# LB_BIT_o9_BARGRAPH-v02_rev1.net
KiCad netlist of a schematic drawn in EAGLE
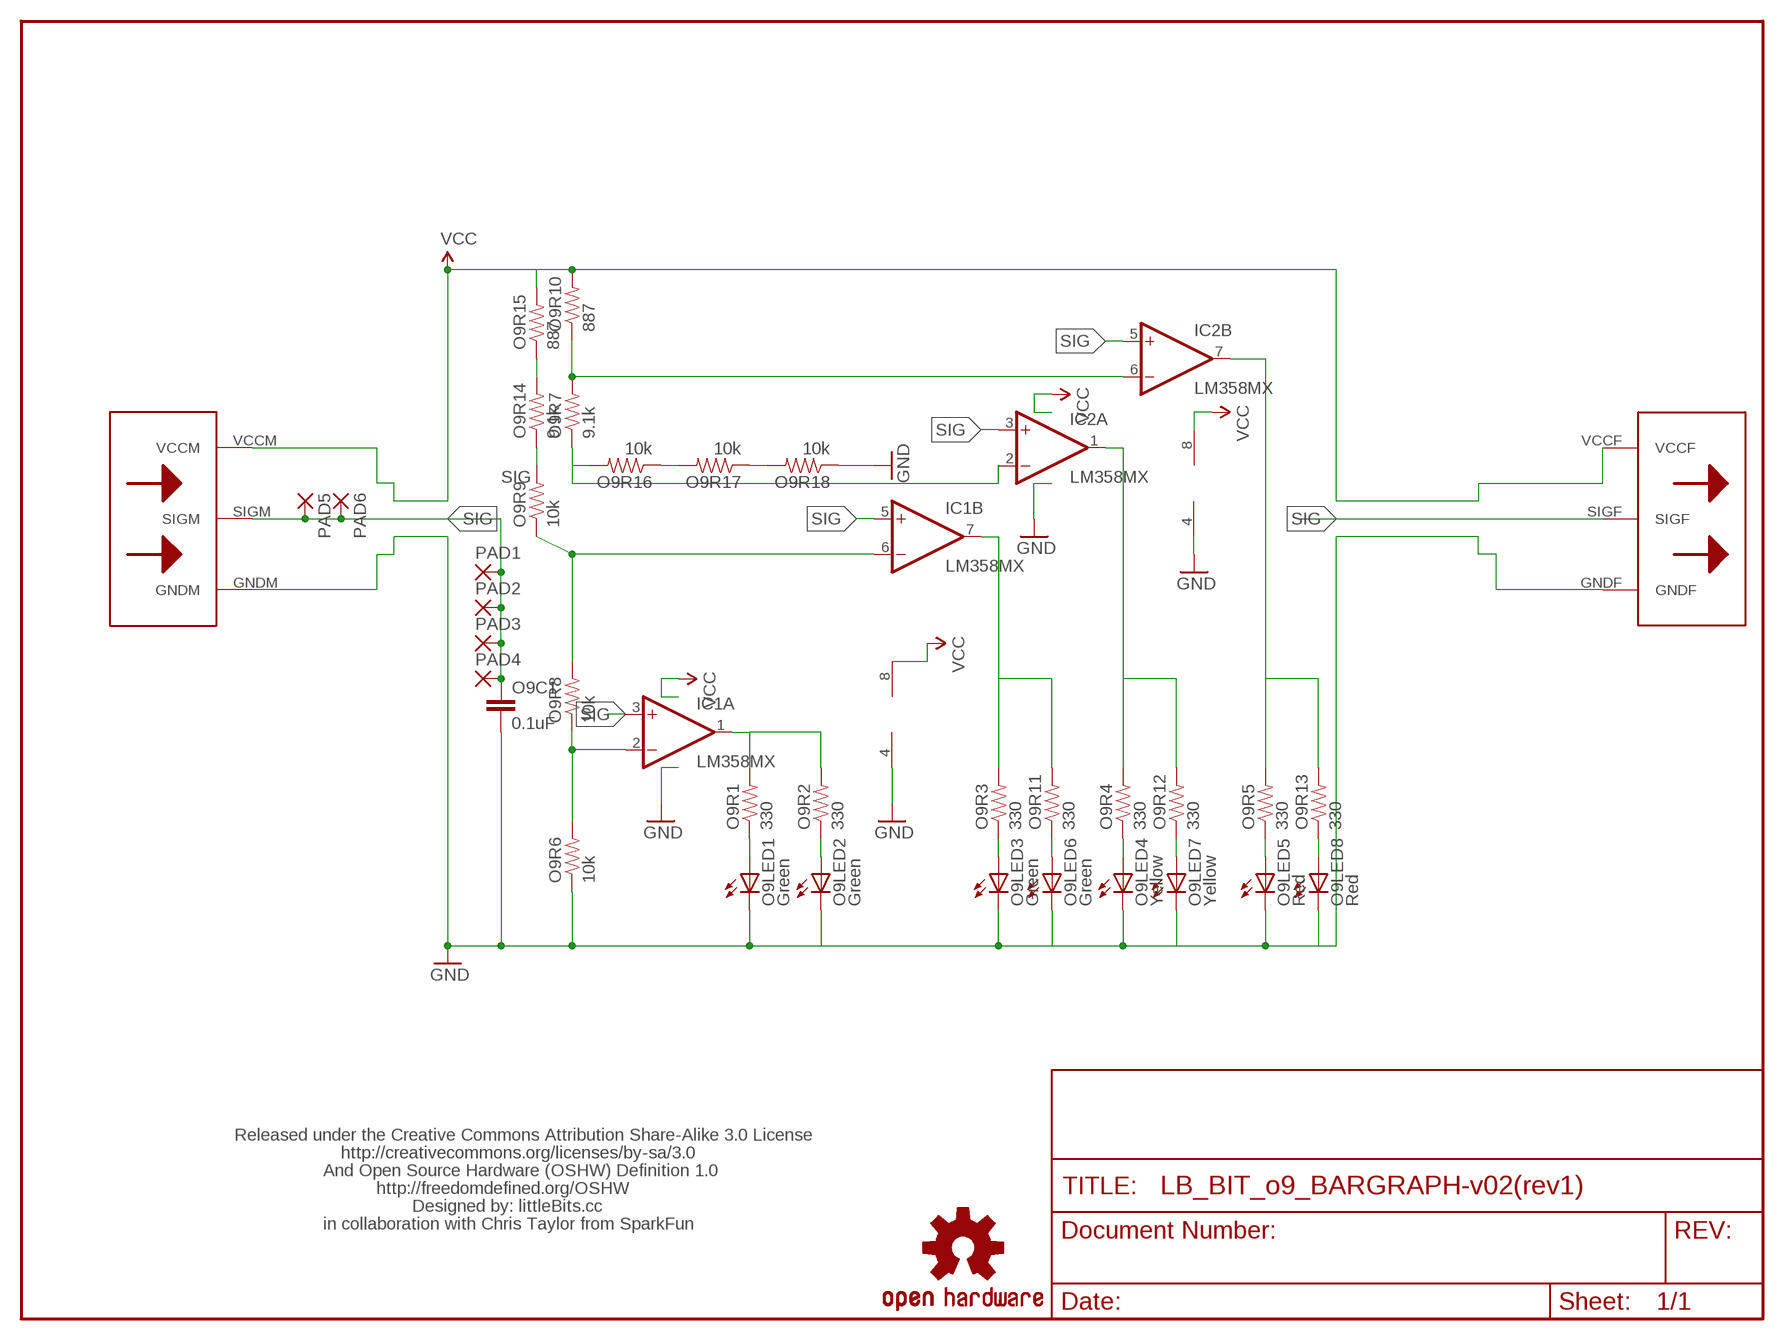
[diagram p0: schematic, sheet 1]

(export (version "E")
  (design (tool "Eeschema 10.0.6"))
  (components
    (comp (ref "IC1")
      (value "LM358MX")
      (footprint "eagle-import:SO08")
      (libsource (lib "eagle-import") (part "LM358MX"))
    )
    (comp (ref "IC2")
      (value "LM358MX")
      (footprint "eagle-import:SO08")
      (libsource (lib "eagle-import") (part "LM358MX"))
    )
    (comp (ref "O9C1")
      (value "0.1uF")
      (footprint "eagle-import:0603-CAP")
      (libsource (lib "eagle-import") (part "CAP0603-CAP"))
    )
    (comp (ref "O9LED1")
      (value "Green")
      (footprint "eagle-import:LED-1206")
      (libsource (lib "eagle-import") (part "LED1206"))
    )
    (comp (ref "O9LED2")
      (value "Green")
      (footprint "eagle-import:LED-1206")
      (libsource (lib "eagle-import") (part "LED1206"))
    )
    (comp (ref "O9LED3")
      (value "Green")
      (footprint "eagle-import:LED-1206")
      (libsource (lib "eagle-import") (part "LED1206"))
    )
    (comp (ref "O9LED4")
      (value "Yellow")
      (footprint "eagle-import:LED-1206")
      (libsource (lib "eagle-import") (part "LED1206"))
    )
    (comp (ref "O9LED5")
      (value "Red")
      (footprint "eagle-import:LED-1206")
      (libsource (lib "eagle-import") (part "LED1206"))
    )
    (comp (ref "O9LED6")
      (value "Green")
      (footprint "eagle-import:LED-1206")
      (libsource (lib "eagle-import") (part "LED1206"))
    )
    (comp (ref "O9LED7")
      (value "Yellow")
      (footprint "eagle-import:LED-1206")
      (libsource (lib "eagle-import") (part "LED1206"))
    )
    (comp (ref "O9LED8")
      (value "Red")
      (footprint "eagle-import:LED-1206")
      (libsource (lib "eagle-import") (part "LED1206"))
    )
    (comp (ref "O9R1")
      (value "330")
      (footprint "eagle-import:0805")
      (libsource (lib "eagle-import") (part "RESISTOR"))
    )
    (comp (ref "O9R2")
      (value "330")
      (footprint "eagle-import:0805")
      (libsource (lib "eagle-import") (part "RESISTOR"))
    )
    (comp (ref "O9R3")
      (value "330")
      (footprint "eagle-import:0805")
      (libsource (lib "eagle-import") (part "RESISTOR"))
    )
    (comp (ref "O9R4")
      (value "330")
      (footprint "eagle-import:0805")
      (libsource (lib "eagle-import") (part "RESISTOR"))
    )
    (comp (ref "O9R5")
      (value "330")
      (footprint "eagle-import:0805")
      (libsource (lib "eagle-import") (part "RESISTOR"))
    )
    (comp (ref "O9R6")
      (value "10k")
      (footprint "eagle-import:0805")
      (libsource (lib "eagle-import") (part "RESISTOR"))
    )
    (comp (ref "O9R7")
      (value "9.1k")
      (footprint "eagle-import:0805")
      (libsource (lib "eagle-import") (part "RESISTOR"))
    )
    (comp (ref "O9R8")
      (value "10k")
      (footprint "eagle-import:0805")
      (libsource (lib "eagle-import") (part "RESISTOR"))
    )
    (comp (ref "O9R9")
      (value "10k")
      (footprint "eagle-import:0805")
      (libsource (lib "eagle-import") (part "RESISTOR"))
    )
    (comp (ref "O9R10")
      (value "887")
      (footprint "eagle-import:0805")
      (libsource (lib "eagle-import") (part "RESISTOR"))
    )
    (comp (ref "O9R11")
      (value "330")
      (footprint "eagle-import:0805")
      (libsource (lib "eagle-import") (part "RESISTOR"))
    )
    (comp (ref "O9R12")
      (value "330")
      (footprint "eagle-import:0805")
      (libsource (lib "eagle-import") (part "RESISTOR"))
    )
    (comp (ref "O9R13")
      (value "330")
      (footprint "eagle-import:0805")
      (libsource (lib "eagle-import") (part "RESISTOR"))
    )
    (comp (ref "O9R14")
      (value "9.1k")
      (footprint "eagle-import:0805")
      (libsource (lib "eagle-import") (part "RESISTOR"))
    )
    (comp (ref "O9R15")
      (value "887")
      (footprint "eagle-import:0805")
      (libsource (lib "eagle-import") (part "RESISTOR"))
    )
    (comp (ref "O9R16")
      (value "10k")
      (footprint "eagle-import:0805")
      (libsource (lib "eagle-import") (part "RESISTOR"))
    )
    (comp (ref "O9R17")
      (value "10k")
      (footprint "eagle-import:0805")
      (libsource (lib "eagle-import") (part "RESISTOR"))
    )
    (comp (ref "O9R18")
      (value "10k")
      (footprint "eagle-import:0805")
      (libsource (lib "eagle-import") (part "RESISTOR"))
    )
    (comp (ref "PAD1")
      (value "SMD2")
      (footprint "eagle-import:SMD1,27-2,54")
      (libsource (lib "eagle-import") (part "SMD2"))
    )
    (comp (ref "PAD2")
      (value "SMD2")
      (footprint "eagle-import:SMD1,27-2,54")
      (libsource (lib "eagle-import") (part "SMD2"))
    )
    (comp (ref "PAD3")
      (value "SMD2")
      (footprint "eagle-import:SMD1,27-2,54")
      (libsource (lib "eagle-import") (part "SMD2"))
    )
    (comp (ref "PAD4")
      (value "SMD2")
      (footprint "eagle-import:SMD1,27-2,54")
      (libsource (lib "eagle-import") (part "SMD2"))
    )
    (comp (ref "PAD5")
      (value "SMD2")
      (footprint "eagle-import:SMD1,27-2,54")
      (libsource (lib "eagle-import") (part "SMD2"))
    )
    (comp (ref "PAD6")
      (value "SMD2")
      (footprint "eagle-import:SMD1,27-2,54")
      (libsource (lib "eagle-import") (part "SMD2"))
    )
    (comp (ref "U$1")
      (value "LB_CREDITS")
      (footprint "eagle-import:OSHWCREDIT")
      (libsource (lib "eagle-import") (part "LB_CREDITS"))
    )
    (comp (ref "U$3")
      (value "OSHW-LOGOL")
      (footprint "eagle-import:OSHW-LOGO-L")
      (libsource (lib "eagle-import") (part "OSHW-LOGOL"))
    )
    (comp (ref "U$7")
      (value "BIGBIT")
      (footprint "eagle-import:BIGBIT")
      (libsource (lib "eagle-import") (part "BIGBIT"))
    )
  )
  (nets
    (net (code "1") (name "GND") (class "Default")
      (node (ref "IC1") (pin "4") (pinfunction "V-_4") (pintype "power_in"))
      (node (ref "IC2") (pin "4") (pinfunction "V-_4") (pintype "power_in"))
      (node (ref "O9C1") (pin "2") (pinfunction "2_2") (pintype "passive"))
      (node (ref "O9LED1") (pin "C") (pinfunction "C_C") (pintype "passive"))
      (node (ref "O9LED2") (pin "C") (pinfunction "C_C") (pintype "passive"))
      (node (ref "O9LED3") (pin "C") (pinfunction "C_C") (pintype "passive"))
      (node (ref "O9LED4") (pin "C") (pinfunction "C_C") (pintype "passive"))
      (node (ref "O9LED5") (pin "C") (pinfunction "C_C") (pintype "passive"))
      (node (ref "O9LED6") (pin "C") (pinfunction "C_C") (pintype "passive"))
      (node (ref "O9LED7") (pin "C") (pinfunction "C_C") (pintype "passive"))
      (node (ref "O9LED8") (pin "C") (pinfunction "C_C") (pintype "passive"))
      (node (ref "O9R18") (pin "1") (pinfunction "1_1") (pintype "passive"))
      (node (ref "O9R6") (pin "1") (pinfunction "1_1") (pintype "passive"))
      (node (ref "U$7") (pin "GNDF") (pinfunction "GNDF_GNDF") (pintype "bidirectional"))
      (node (ref "U$7") (pin "GNDM") (pinfunction "GNDM_GNDM") (pintype "bidirectional"))
    )
    (net (code "2") (name "Net-(IC1A--IN)") (class "Default")
      (node (ref "IC1") (pin "2") (pinfunction "-IN_2") (pintype "input"))
      (node (ref "O9R6") (pin "2") (pinfunction "2_2") (pintype "passive"))
      (node (ref "O9R8") (pin "1") (pinfunction "1_1") (pintype "passive"))
    )
    (net (code "3") (name "Net-(IC1A-OUT)") (class "Default")
      (node (ref "IC1") (pin "1") (pinfunction "OUT_1") (pintype "output"))
      (node (ref "O9R1") (pin "2") (pinfunction "2_2") (pintype "passive"))
      (node (ref "O9R2") (pin "2") (pinfunction "2_2") (pintype "passive"))
    )
    (net (code "4") (name "Net-(IC1B--IN)") (class "Default")
      (node (ref "IC1") (pin "6") (pinfunction "-IN_6") (pintype "input"))
      (node (ref "O9R8") (pin "2") (pinfunction "2_2") (pintype "passive"))
      (node (ref "O9R9") (pin "1") (pinfunction "1_1") (pintype "passive"))
    )
    (net (code "5") (name "Net-(IC1B-OUT)") (class "Default")
      (node (ref "IC1") (pin "7") (pinfunction "OUT_7") (pintype "output"))
      (node (ref "O9R11") (pin "2") (pinfunction "2_2") (pintype "passive"))
      (node (ref "O9R3") (pin "2") (pinfunction "2_2") (pintype "passive"))
    )
    (net (code "6") (name "Net-(IC2A--IN)") (class "Default")
      (node (ref "IC2") (pin "2") (pinfunction "-IN_2") (pintype "input"))
      (node (ref "O9R16") (pin "2") (pinfunction "2_2") (pintype "passive"))
      (node (ref "O9R7") (pin "1") (pinfunction "1_1") (pintype "passive"))
    )
    (net (code "7") (name "Net-(IC2A-OUT)") (class "Default")
      (node (ref "IC2") (pin "1") (pinfunction "OUT_1") (pintype "output"))
      (node (ref "O9R12") (pin "2") (pinfunction "2_2") (pintype "passive"))
      (node (ref "O9R4") (pin "2") (pinfunction "2_2") (pintype "passive"))
    )
    (net (code "8") (name "Net-(IC2B--IN)") (class "Default")
      (node (ref "IC2") (pin "6") (pinfunction "-IN_6") (pintype "input"))
      (node (ref "O9R10") (pin "1") (pinfunction "1_1") (pintype "passive"))
      (node (ref "O9R7") (pin "2") (pinfunction "2_2") (pintype "passive"))
    )
    (net (code "9") (name "Net-(IC2B-OUT)") (class "Default")
      (node (ref "IC2") (pin "7") (pinfunction "OUT_7") (pintype "output"))
      (node (ref "O9R13") (pin "2") (pinfunction "2_2") (pintype "passive"))
      (node (ref "O9R5") (pin "2") (pinfunction "2_2") (pintype "passive"))
    )
    (net (code "10") (name "Net-(O9LED1-PadA)") (class "Default")
      (node (ref "O9LED1") (pin "A") (pinfunction "A_A") (pintype "passive"))
      (node (ref "O9R1") (pin "1") (pinfunction "1_1") (pintype "passive"))
    )
    (net (code "11") (name "Net-(O9LED2-PadA)") (class "Default")
      (node (ref "O9LED2") (pin "A") (pinfunction "A_A") (pintype "passive"))
      (node (ref "O9R2") (pin "1") (pinfunction "1_1") (pintype "passive"))
    )
    (net (code "12") (name "Net-(O9LED3-PadA)") (class "Default")
      (node (ref "O9LED3") (pin "A") (pinfunction "A_A") (pintype "passive"))
      (node (ref "O9R3") (pin "1") (pinfunction "1_1") (pintype "passive"))
    )
    (net (code "13") (name "Net-(O9LED4-PadA)") (class "Default")
      (node (ref "O9LED4") (pin "A") (pinfunction "A_A") (pintype "passive"))
      (node (ref "O9R4") (pin "1") (pinfunction "1_1") (pintype "passive"))
    )
    (net (code "14") (name "Net-(O9LED5-PadA)") (class "Default")
      (node (ref "O9LED5") (pin "A") (pinfunction "A_A") (pintype "passive"))
      (node (ref "O9R5") (pin "1") (pinfunction "1_1") (pintype "passive"))
    )
    (net (code "15") (name "Net-(O9LED6-PadA)") (class "Default")
      (node (ref "O9LED6") (pin "A") (pinfunction "A_A") (pintype "passive"))
      (node (ref "O9R11") (pin "1") (pinfunction "1_1") (pintype "passive"))
    )
    (net (code "16") (name "Net-(O9LED7-PadA)") (class "Default")
      (node (ref "O9LED7") (pin "A") (pinfunction "A_A") (pintype "passive"))
      (node (ref "O9R12") (pin "1") (pinfunction "1_1") (pintype "passive"))
    )
    (net (code "17") (name "Net-(O9LED8-PadA)") (class "Default")
      (node (ref "O9LED8") (pin "A") (pinfunction "A_A") (pintype "passive"))
      (node (ref "O9R13") (pin "1") (pinfunction "1_1") (pintype "passive"))
    )
    (net (code "18") (name "Net-(O9R14-Pad1)") (class "Default")
      (node (ref "O9R14") (pin "1") (pinfunction "1_1") (pintype "passive"))
      (node (ref "O9R9") (pin "2") (pinfunction "2_2") (pintype "passive"))
    )
    (net (code "19") (name "Net-(O9R14-Pad2)") (class "Default")
      (node (ref "O9R14") (pin "2") (pinfunction "2_2") (pintype "passive"))
      (node (ref "O9R15") (pin "1") (pinfunction "1_1") (pintype "passive"))
    )
    (net (code "20") (name "Net-(O9R16-Pad1)") (class "Default")
      (node (ref "O9R16") (pin "1") (pinfunction "1_1") (pintype "passive"))
      (node (ref "O9R17") (pin "2") (pinfunction "2_2") (pintype "passive"))
    )
    (net (code "21") (name "Net-(O9R17-Pad1)") (class "Default")
      (node (ref "O9R17") (pin "1") (pinfunction "1_1") (pintype "passive"))
      (node (ref "O9R18") (pin "2") (pinfunction "2_2") (pintype "passive"))
    )
    (net (code "22") (name "SIG") (class "Default")
      (node (ref "IC1") (pin "3") (pinfunction "+IN_3") (pintype "input"))
      (node (ref "IC1") (pin "5") (pinfunction "+IN_5") (pintype "input"))
      (node (ref "IC2") (pin "3") (pinfunction "+IN_3") (pintype "input"))
      (node (ref "IC2") (pin "5") (pinfunction "+IN_5") (pintype "input"))
      (node (ref "O9C1") (pin "1") (pinfunction "1_1") (pintype "passive"))
      (node (ref "PAD1") (pin "1") (pinfunction "P_1") (pintype "passive"))
      (node (ref "PAD2") (pin "1") (pinfunction "P_1") (pintype "passive"))
      (node (ref "PAD3") (pin "1") (pinfunction "P_1") (pintype "passive"))
      (node (ref "PAD4") (pin "1") (pinfunction "P_1") (pintype "passive"))
      (node (ref "PAD5") (pin "1") (pinfunction "P_1") (pintype "passive"))
      (node (ref "PAD6") (pin "1") (pinfunction "P_1") (pintype "passive"))
      (node (ref "U$7") (pin "SIGF") (pinfunction "SIGF_SIGF") (pintype "bidirectional"))
      (node (ref "U$7") (pin "SIGM") (pinfunction "SIGM_SIGM") (pintype "bidirectional"))
    )
    (net (code "23") (name "VCC") (class "Default")
      (node (ref "IC1") (pin "8") (pinfunction "V+_8") (pintype "power_in"))
      (node (ref "IC2") (pin "8") (pinfunction "V+_8") (pintype "power_in"))
      (node (ref "O9R10") (pin "2") (pinfunction "2_2") (pintype "passive"))
      (node (ref "O9R15") (pin "2") (pinfunction "2_2") (pintype "passive"))
      (node (ref "U$7") (pin "VCCF") (pinfunction "VCCF_VCCF") (pintype "bidirectional"))
      (node (ref "U$7") (pin "VCCM") (pinfunction "VCCM_VCCM") (pintype "bidirectional"))
    )
  )
)
